# Main.net
KiCad netlist of a schematic drawn in Altium Designer
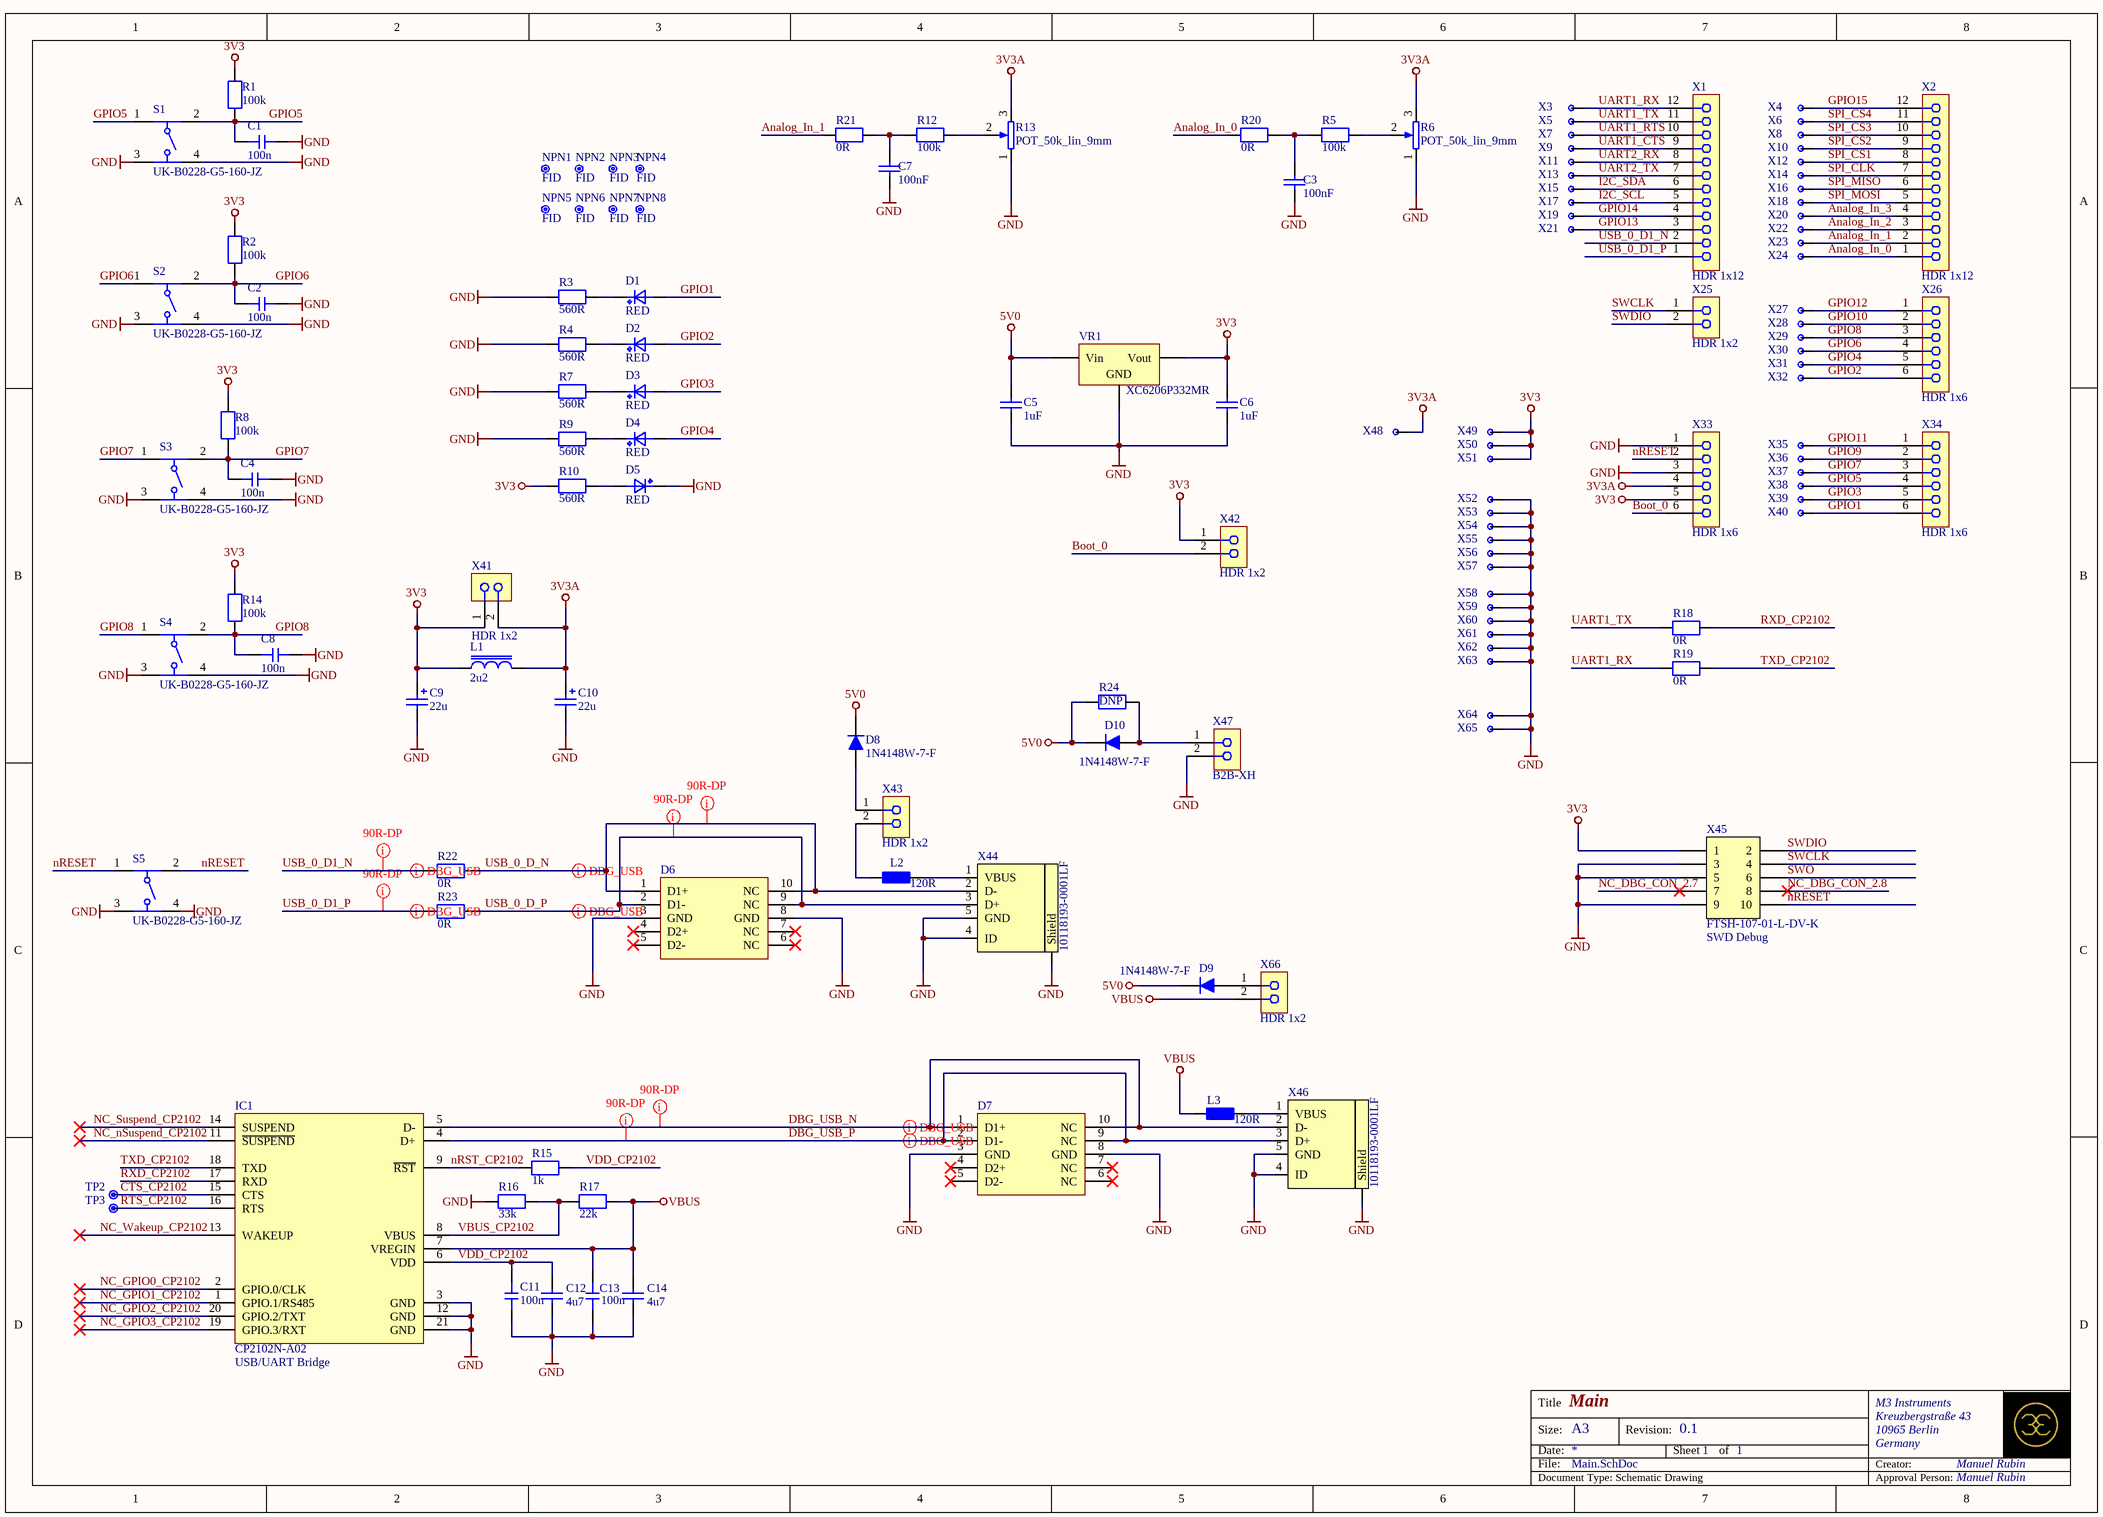
[diagram p0: Main.SchDoc]

(export (version "E")
  (design (tool "Eeschema 10.0.6"))
  (components
    (comp (ref "C1")
      (value "100n")
      (footprint "CAPC1608X95N")
      (description "100n_50V")
      (fields (field (name "MANUFACTURER") "AVX") (field (name "MANUFACTURER PART NUMBER") "06031C104KAT2A"))
      (libsource (lib "Raindancer") (part "C_100n_50V_0603"))
    )
    (comp (ref "C2")
      (value "100n")
      (footprint "CAPC1608X95N")
      (description "100n_50V")
      (fields (field (name "MANUFACTURER") "AVX") (field (name "MANUFACTURER PART NUMBER") "06031C104KAT2A"))
      (libsource (lib "Raindancer") (part "C_100n_50V_0603"))
    )
    (comp (ref "C3")
      (value "100nF")
      (footprint "CAPC1608X95N")
      (description "Multilayer Ceramic Capacitors MLCC - SMD/SMT, 100nF")
      (fields
        (field (name "MANUFACTURER") "YAGEO")
        (field (name "MANUFACTURER PART NUMBER") "CC0603KRX7R9BB104")
      )
      (libsource (lib "Caps") (part "CAP_100nF_0603"))
    )
    (comp (ref "C4")
      (value "100n")
      (footprint "CAPC1608X95N")
      (description "100n_50V")
      (fields (field (name "MANUFACTURER") "AVX") (field (name "MANUFACTURER PART NUMBER") "06031C104KAT2A"))
      (libsource (lib "Raindancer") (part "C_100n_50V_0603"))
    )
    (comp (ref "C5")
      (value "1uF")
      (footprint "CAPC2012X145N")
      (description "Multilayer Ceramic Capacitors MLCC - SMD/SMT, 1uF")
      (fields (field (name "MANUFACTURER") "Samsung Electro-Mechanics") (field (name "TOLERANCE") "10%"))
      (libsource (lib "Caps") (part "CAP_1uF_0805"))
    )
    (comp (ref "C6")
      (value "1uF")
      (footprint "CAPC2012X145N")
      (description "Multilayer Ceramic Capacitors MLCC - SMD/SMT, 1uF")
      (fields (field (name "MANUFACTURER") "Samsung Electro-Mechanics") (field (name "TOLERANCE") "10%"))
      (libsource (lib "Caps") (part "CAP_1uF_0805"))
    )
    (comp (ref "C7")
      (value "100nF")
      (footprint "CAPC1608X95N")
      (description "Multilayer Ceramic Capacitors MLCC - SMD/SMT, 100nF")
      (fields
        (field (name "MANUFACTURER") "YAGEO")
        (field (name "MANUFACTURER PART NUMBER") "CC0603KRX7R9BB104")
      )
      (libsource (lib "Caps") (part "CAP_100nF_0603"))
    )
    (comp (ref "C8")
      (value "100n")
      (footprint "CAPC1608X95N")
      (description "100n_50V")
      (fields (field (name "MANUFACTURER") "AVX") (field (name "MANUFACTURER PART NUMBER") "06031C104KAT2A"))
      (libsource (lib "Raindancer") (part "C_100n_50V_0603"))
    )
    (comp (ref "C9")
      (value "22u")
      (footprint "CAPAE4643X54M")
      (description "Aluminium Electrolytic Capacitors - SMD 22UF 16V HA SMD")
      (fields
        (field (name "MANUFACTURER") "Panasonic")
        (field (name "MANUFACTURER PART NUMBER") "EEE-HAC220WAR")
      )
      (libsource (lib "Caps") (part "CAP_22u"))
    )
    (comp (ref "C10")
      (value "22u")
      (footprint "CAPAE4643X54M")
      (description "Aluminium Electrolytic Capacitors - SMD 22UF 16V HA SMD")
      (fields
        (field (name "MANUFACTURER") "Panasonic")
        (field (name "MANUFACTURER PART NUMBER") "EEE-HAC220WAR")
      )
      (libsource (lib "Caps") (part "CAP_22u"))
    )
    (comp (ref "C11")
      (value "100n")
      (footprint "CAPC1608X95N")
      (description "100n_50V")
      (fields (field (name "MANUFACTURER") "AVX") (field (name "MANUFACTURER PART NUMBER") "06031C104KAT2A"))
      (libsource (lib "Raindancer") (part "C_100n_50V_0603"))
    )
    (comp (ref "C12")
      (value "4u7")
      (footprint "CAPC1608X95N")
      (description "16V 4.7uF X5R ±10% 0603 Multilayer Ceramic Capacitors MLCC - SMD/SMT ROHS")
      (fields
        (field (name "MANUFACTURER") "Murata Electronics")
        (field (name "MANUFACTURER PART NUMBER") "GRM188C81C475KE11D")
      )
      (libsource (lib "Caps") (part "CAP_4u7_0603"))
    )
    (comp (ref "C13")
      (value "100n")
      (footprint "CAPC1608X95N")
      (description "100n_50V")
      (fields (field (name "MANUFACTURER") "AVX") (field (name "MANUFACTURER PART NUMBER") "06031C104KAT2A"))
      (libsource (lib "Raindancer") (part "C_100n_50V_0603"))
    )
    (comp (ref "C14")
      (value "4u7")
      (footprint "CAPC1608X95N")
      (description "16V 4.7uF X5R ±10% 0603 Multilayer Ceramic Capacitors MLCC - SMD/SMT ROHS")
      (fields
        (field (name "MANUFACTURER") "Murata Electronics")
        (field (name "MANUFACTURER PART NUMBER") "GRM188C81C475KE11D")
      )
      (libsource (lib "Caps") (part "CAP_4u7_0603"))
    )
    (comp (ref "D1")
      (value "RED")
      (footprint "WL-SMCW_0805")
      (description "Standard LEDs - SMD WL-SMCW SMDMono TpVw Waterclr 0805 Red")
      (fields
        (field (name "MANUFACTURER") "Wurth Elektronik")
        (field (name "MANUFACTURER PART NUMBER") "150080RS75000")
      )
      (libsource (lib "Diodes") (part "LED_0805_RED_AK"))
    )
    (comp (ref "D2")
      (value "RED")
      (footprint "WL-SMCW_0805")
      (description "Standard LEDs - SMD WL-SMCW SMDMono TpVw Waterclr 0805 Red")
      (fields
        (field (name "MANUFACTURER") "Wurth Elektronik")
        (field (name "MANUFACTURER PART NUMBER") "150080RS75000")
      )
      (libsource (lib "Diodes") (part "LED_0805_RED_AK"))
    )
    (comp (ref "D3")
      (value "RED")
      (footprint "WL-SMCW_0805")
      (description "Standard LEDs - SMD WL-SMCW SMDMono TpVw Waterclr 0805 Red")
      (fields
        (field (name "MANUFACTURER") "Wurth Elektronik")
        (field (name "MANUFACTURER PART NUMBER") "150080RS75000")
      )
      (libsource (lib "Diodes") (part "LED_0805_RED_AK"))
    )
    (comp (ref "D4")
      (value "RED")
      (footprint "WL-SMCW_0805")
      (description "Standard LEDs - SMD WL-SMCW SMDMono TpVw Waterclr 0805 Red")
      (fields
        (field (name "MANUFACTURER") "Wurth Elektronik")
        (field (name "MANUFACTURER PART NUMBER") "150080RS75000")
      )
      (libsource (lib "Diodes") (part "LED_0805_RED_AK"))
    )
    (comp (ref "D5")
      (value "RED")
      (footprint "WL-SMCW_0805")
      (description "Standard LEDs - SMD WL-SMCW SMDMono TpVw Waterclr 0805 Red")
      (fields
        (field (name "MANUFACTURER") "Wurth Elektronik")
        (field (name "MANUFACTURER PART NUMBER") "150080RS75000")
      )
      (libsource (lib "Diodes") (part "LED_0805_RED_AK"))
    )
    (comp (ref "D6")
      (value "~")
      (footprint "DQA R-PUSON-N10")
      (description "2-, 4-Channel ESD Protection for Super-Speed USB 3.0 Interface")
      (fields
        (field (name "MANUFACTURER") "Texas Instruments")
        (field (name "MANUFACTURER PART NUMBER") "TPD4EUSB30DQAR")
      )
      (libsource (lib "Diodes") (part "TPD4EUSB30DQAR"))
    )
    (comp (ref "D7")
      (value "~")
      (footprint "DQA R-PUSON-N10")
      (description "2-, 4-Channel ESD Protection for Super-Speed USB 3.0 Interface")
      (fields
        (field (name "MANUFACTURER") "Texas Instruments")
        (field (name "MANUFACTURER PART NUMBER") "TPD4EUSB30DQAR")
      )
      (libsource (lib "Diodes") (part "TPD4EUSB30DQAR"))
    )
    (comp (ref "D8")
      (value "1N4148W-7-F")
      (footprint "SOD-123")
      (description "Diodes - General Purpose, Power, Switching SURFACE MOUNT FAST SWITCHING DIODE 2A")
      (fields (field (name "MANUFACTURER") "Diodes Incorporated"))
      (libsource (lib "Diodes") (part "1N4148W-7-F"))
    )
    (comp (ref "D9")
      (value "1N4148W-7-F")
      (footprint "SOD-123")
      (description "Diodes - General Purpose, Power, Switching SURFACE MOUNT FAST SWITCHING DIODE 2A")
      (fields (field (name "MANUFACTURER") "Diodes Incorporated"))
      (libsource (lib "Diodes") (part "1N4148W-7-F"))
    )
    (comp (ref "D10")
      (value "1N4148W-7-F")
      (footprint "SOD-123")
      (description "Diodes - General Purpose, Power, Switching SURFACE MOUNT FAST SWITCHING DIODE 2A")
      (fields (field (name "MANUFACTURER") "Diodes Incorporated"))
      (libsource (lib "Diodes") (part "1N4148W-7-F"))
    )
    (comp (ref "IC1")
      (value "CP2102N-A02")
      (footprint "SILABS_CP2102N-A02-GQFN20R")
      (description "USB Interface IC USBXpress - USB to UART Bridge QFN28")
      (fields
        (field (name "MANUFACTURER") "Silicon Labs")
        (field (name "MANUFACTURER PART NUMBER") "CP2102N-A02-GQFN20R")
        (field (name "DEVNOTE") "USB/UART Bridge")
      )
      (libsource (lib "Raindancer") (part "IC_CP2102N-A02-QFN20"))
    )
    (comp (ref "L1")
      (value "2u2")
      (footprint "INDP5050X39N")
      (description "Fixed Inductors 2.2uH 3.8A")
      (fields
        (field (name "MANUFACTURER") "Bourns")
        (field (name "MANUFACTURER PART NUMBER") "SRN5040TA-2R2M")
      )
      (libsource (lib "Inductors") (part "IND_2u2_3.8A"))
    )
    (comp (ref "L2")
      (value "120R")
      (footprint "INDC1608X95AN")
      (description "Chip Bead Inductors for Power Lines")
      (fields
        (field (name "MANUFACTURER") "Taiyo Yuden")
        (field (name "MANUFACTURER PART NUMBER") "FBMH1608HL121-T")
      )
      (libsource (lib "Inductors") (part "FB_600R_0603"))
    )
    (comp (ref "L3")
      (value "120R")
      (footprint "INDC1608X95AN")
      (description "Chip Bead Inductors for Power Lines")
      (fields
        (field (name "MANUFACTURER") "Taiyo Yuden")
        (field (name "MANUFACTURER PART NUMBER") "FBMH1608HL121-T")
      )
      (libsource (lib "Inductors") (part "FB_600R_0603"))
    )
    (comp (ref "NPN1")
      (value "FID")
      (footprint "Fiducial_1mm")
      (libsource (lib "MISC") (part "Fiducial_1mm"))
    )
    (comp (ref "NPN2")
      (value "FID")
      (footprint "Fiducial_1mm")
      (libsource (lib "MISC") (part "Fiducial_1mm"))
    )
    (comp (ref "NPN3")
      (value "FID")
      (footprint "Fiducial_1mm")
      (libsource (lib "MISC") (part "Fiducial_1mm"))
    )
    (comp (ref "NPN4")
      (value "FID")
      (footprint "Fiducial_1mm")
      (libsource (lib "MISC") (part "Fiducial_1mm"))
    )
    (comp (ref "NPN5")
      (value "FID")
      (footprint "Fiducial_1mm")
      (libsource (lib "MISC") (part "Fiducial_1mm"))
    )
    (comp (ref "NPN6")
      (value "FID")
      (footprint "Fiducial_1mm")
      (libsource (lib "MISC") (part "Fiducial_1mm"))
    )
    (comp (ref "NPN7")
      (value "FID")
      (footprint "Fiducial_1mm")
      (libsource (lib "MISC") (part "Fiducial_1mm"))
    )
    (comp (ref "NPN8")
      (value "FID")
      (footprint "Fiducial_1mm")
      (libsource (lib "MISC") (part "Fiducial_1mm"))
    )
    (comp (ref "R1")
      (value "100k")
      (footprint "RESC2012X70N")
      (description "Thick Film Resistors - SMD 1/8watt 100Kohms 1% 100ppm")
      (fields
        (field (name "MANUFACTURER") "Vishay / Dale")
        (field (name "MANUFACTURER PART NUMBER") "CRCW0805100KFKEA")
      )
      (libsource (lib "Resistors") (part "RES_100k_0805"))
    )
    (comp (ref "R2")
      (value "100k")
      (footprint "RESC2012X70N")
      (description "Thick Film Resistors - SMD 1/8watt 100Kohms 1% 100ppm")
      (fields
        (field (name "MANUFACTURER") "Vishay / Dale")
        (field (name "MANUFACTURER PART NUMBER") "CRCW0805100KFKEA")
      )
      (libsource (lib "Resistors") (part "RES_100k_0805"))
    )
    (comp (ref "R3")
      (value "560R")
      (footprint "RESC1608X55N")
      (description "Thick Film Resistors - SMD 560 Ohms 125 mW 0603")
      (fields
        (field (name "MANUFACTURER") "ROHM Semicon")
        (field (name "MANUFACTURER PART NUMBER") "MCR03ERTF5600")
      )
      (libsource (lib "Resistors") (part "RES_560R_0603"))
    )
    (comp (ref "R4")
      (value "560R")
      (footprint "RESC1608X55N")
      (description "Thick Film Resistors - SMD 560 Ohms 125 mW 0603")
      (fields
        (field (name "MANUFACTURER") "ROHM Semicon")
        (field (name "MANUFACTURER PART NUMBER") "MCR03ERTF5600")
      )
      (libsource (lib "Resistors") (part "RES_560R_0603"))
    )
    (comp (ref "R5")
      (value "100k")
      (footprint "RESC2012X70N")
      (description "Thick Film Resistors - SMD 1/8watt 100Kohms 1% 100ppm")
      (fields
        (field (name "MANUFACTURER") "Vishay / Dale")
        (field (name "MANUFACTURER PART NUMBER") "CRCW0805100KFKEA")
      )
      (libsource (lib "") (part "RES_100k_0805_1"))
    )
    (comp (ref "R6")
      (value "POT_50k_lin_9mm")
      (footprint "PTV09")
      (description "PTV09A-4020F-A203 50k, 20mm")
      (fields
        (field (name "MANUFACTURER") "Bourns")
        (field (name "MANUFACTURER PART NUMBER") "PTV09A-5020F-A503")
      )
      (libsource (lib "Resistors") (part "POT_50k_lin_9mm"))
    )
    (comp (ref "R7")
      (value "560R")
      (footprint "RESC1608X55N")
      (description "Thick Film Resistors - SMD 560 Ohms 125 mW 0603")
      (fields
        (field (name "MANUFACTURER") "ROHM Semicon")
        (field (name "MANUFACTURER PART NUMBER") "MCR03ERTF5600")
      )
      (libsource (lib "Resistors") (part "RES_560R_0603"))
    )
    (comp (ref "R8")
      (value "100k")
      (footprint "RESC2012X70N")
      (description "Thick Film Resistors - SMD 1/8watt 100Kohms 1% 100ppm")
      (fields
        (field (name "MANUFACTURER") "Vishay / Dale")
        (field (name "MANUFACTURER PART NUMBER") "CRCW0805100KFKEA")
      )
      (libsource (lib "Resistors") (part "RES_100k_0805"))
    )
    (comp (ref "R9")
      (value "560R")
      (footprint "RESC1608X55N")
      (description "Thick Film Resistors - SMD 560 Ohms 125 mW 0603")
      (fields
        (field (name "MANUFACTURER") "ROHM Semicon")
        (field (name "MANUFACTURER PART NUMBER") "MCR03ERTF5600")
      )
      (libsource (lib "Resistors") (part "RES_560R_0603"))
    )
    (comp (ref "R10")
      (value "560R")
      (footprint "RESC1608X55N")
      (description "Thick Film Resistors - SMD 560 Ohms 125 mW 0603")
      (fields
        (field (name "MANUFACTURER") "ROHM Semicon")
        (field (name "MANUFACTURER PART NUMBER") "MCR03ERTF5600")
      )
      (libsource (lib "Resistors") (part "RES_560R_0603"))
    )
    (comp (ref "R12")
      (value "100k")
      (footprint "RESC2012X70N")
      (description "Thick Film Resistors - SMD 1/8watt 100Kohms 1% 100ppm")
      (fields
        (field (name "MANUFACTURER") "Vishay / Dale")
        (field (name "MANUFACTURER PART NUMBER") "CRCW0805100KFKEA")
      )
      (libsource (lib "") (part "RES_100k_0805_1"))
    )
    (comp (ref "R13")
      (value "POT_50k_lin_9mm")
      (footprint "PTV09")
      (description "PTV09A-4020F-A203 50k, 20mm")
      (fields
        (field (name "MANUFACTURER") "Bourns")
        (field (name "MANUFACTURER PART NUMBER") "PTV09A-5020F-A503")
      )
      (libsource (lib "Resistors") (part "POT_50k_lin_9mm"))
    )
    (comp (ref "R14")
      (value "100k")
      (footprint "RESC2012X70N")
      (description "Thick Film Resistors - SMD 1/8watt 100Kohms 1% 100ppm")
      (fields
        (field (name "MANUFACTURER") "Vishay / Dale")
        (field (name "MANUFACTURER PART NUMBER") "CRCW0805100KFKEA")
      )
      (libsource (lib "Resistors") (part "RES_100k_0805"))
    )
    (comp (ref "R15")
      (value "1k")
      (footprint "RESC1608X55AN")
      (description "Thick Film Resistors - SMD 1 kOhms 100mW 0603 1%")
      (fields
        (field (name "MANUFACTURER") "Yageo")
        (field (name "MANUFACTURER PART NUMBER") "RC0603FR-071KL")
      )
      (libsource (lib "Raindancer") (part "RES_1k_0603"))
    )
    (comp (ref "R16")
      (value "33k")
      (footprint "RESC1608X55AN")
      (description "Thick Film Resistors - SMD 33 kOhms 100 mW 0603 5%")
      (fields
        (field (name "MANUFACTURER") "YAGEO")
        (field (name "MANUFACTURER PART NUMBER") "RC0603JR-0733KL")
      )
      (libsource (lib "Raindancer") (part "RES_33k_0603"))
    )
    (comp (ref "R17")
      (value "22k")
      (footprint "RESC1608X55AN")
      (description "Thick Film Resistors - SMD 22kOhms 1/10W 0603 1%")
      (fields
        (field (name "MANUFACTURER") "YAGEO")
        (field (name "MANUFACTURER PART NUMBER") "RC0603FR-7W22KL")
      )
      (libsource (lib "Raindancer") (part "RES_22k_0603"))
    )
    (comp (ref "R18")
      (value "0R")
      (footprint "RESC1608X55N")
      (description "Thick Film Resistors - SMD 1/10watt ZEROohm Jumper")
      (fields
        (field (name "MANUFACTURER") "Vishay")
        (field (name "MANUFACTURER PART NUMBER") "CRCW06030000Z0EA")
      )
      (libsource (lib "Resistors") (part "RES_0R_0603"))
    )
    (comp (ref "R19")
      (value "0R")
      (footprint "RESC1608X55N")
      (description "Thick Film Resistors - SMD 1/10watt ZEROohm Jumper")
      (fields
        (field (name "MANUFACTURER") "Vishay")
        (field (name "MANUFACTURER PART NUMBER") "CRCW06030000Z0EA")
      )
      (libsource (lib "Resistors") (part "RES_0R_0603"))
    )
    (comp (ref "R20")
      (value "0R")
      (footprint "RESC1608X55N")
      (description "Thick Film Resistors - SMD 1/10watt ZEROohm Jumper")
      (fields
        (field (name "MANUFACTURER") "Vishay")
        (field (name "MANUFACTURER PART NUMBER") "CRCW06030000Z0EA")
      )
      (libsource (lib "Resistors") (part "RES_0R_0603"))
    )
    (comp (ref "R21")
      (value "0R")
      (footprint "RESC1608X55N")
      (description "Thick Film Resistors - SMD 1/10watt ZEROohm Jumper")
      (fields
        (field (name "MANUFACTURER") "Vishay")
        (field (name "MANUFACTURER PART NUMBER") "CRCW06030000Z0EA")
      )
      (libsource (lib "Resistors") (part "RES_0R_0603"))
    )
    (comp (ref "R22")
      (value "0R")
      (footprint "RESC1608X55N")
      (description "Thick Film Resistors - SMD 1/10watt ZEROohm Jumper")
      (fields
        (field (name "MANUFACTURER") "Vishay")
        (field (name "MANUFACTURER PART NUMBER") "CRCW06030000Z0EA")
      )
      (libsource (lib "Resistors") (part "RES_0R_0603"))
    )
    (comp (ref "R23")
      (value "0R")
      (footprint "RESC1608X55N")
      (description "Thick Film Resistors - SMD 1/10watt ZEROohm Jumper")
      (fields
        (field (name "MANUFACTURER") "Vishay")
        (field (name "MANUFACTURER PART NUMBER") "CRCW06030000Z0EA")
      )
      (libsource (lib "Resistors") (part "RES_0R_0603"))
    )
    (comp (ref "R24")
      (value "DNP")
      (footprint "RESC2012X70N")
      (description "Resistor SMD 0805 - not populated")
      (libsource (lib "Resistors") (part "RES_DNF_0805"))
    )
    (comp (ref "S1")
      (value "UK-B0228-G5-160-JZ")
      (footprint "UK-B0228-G5-160-JZ")
      (fields (field (name "MANUFACTURER") "USAKRO"))
      (libsource (lib "Switches") (part "SW_UK-B0228-G5-160-JZ"))
    )
    (comp (ref "S2")
      (value "UK-B0228-G5-160-JZ")
      (footprint "UK-B0228-G5-160-JZ")
      (fields (field (name "MANUFACTURER") "USAKRO"))
      (libsource (lib "Switches") (part "SW_UK-B0228-G5-160-JZ"))
    )
    (comp (ref "S3")
      (value "UK-B0228-G5-160-JZ")
      (footprint "UK-B0228-G5-160-JZ")
      (fields (field (name "MANUFACTURER") "USAKRO"))
      (libsource (lib "Switches") (part "SW_UK-B0228-G5-160-JZ"))
    )
    (comp (ref "S4")
      (value "UK-B0228-G5-160-JZ")
      (footprint "UK-B0228-G5-160-JZ")
      (fields (field (name "MANUFACTURER") "USAKRO"))
      (libsource (lib "Switches") (part "SW_UK-B0228-G5-160-JZ"))
    )
    (comp (ref "S5")
      (value "UK-B0228-G5-160-JZ")
      (footprint "UK-B0228-G5-160-JZ")
      (fields (field (name "MANUFACTURER") "USAKRO"))
      (libsource (lib "Switches") (part "SW_UK-B0228-G5-160-JZ"))
    )
    (comp (ref "TP2")
      (value "TP 0.7mm")
      (footprint "TP_0.7mm")
      (description "Test Pad surface mount")
      (libsource (lib "Raindancer") (part "MISC_Test Pad 0.7mm"))
    )
    (comp (ref "TP3")
      (value "TP 0.7mm")
      (footprint "TP_0.7mm")
      (description "Test Pad surface mount")
      (libsource (lib "Raindancer") (part "MISC_Test Pad 0.7mm"))
    )
    (comp (ref "VR1")
      (value "XC6206P332MR")
      (footprint "SOT95P280X135-3N_123")
      (description "LOW DROPOUT REGULATORS(LDO) POSITIVE FIXED 680MV @ 100MA 6V 3.3V 200MA SOT-23-3L ROHS")
      (fields (field (name "MANUFACTURER") "Torex Semicon"))
      (libsource (lib "ICs") (part "IC_XC6206P332MR"))
    )
    (comp (ref "X1")
      (value "HDR 1x12")
      (footprint "61301211821_NO")
      (description "Board-to-Board-Steckverbinder, 2.54 mm, 12 Kontakt(e), Stiftleiste 1-Reihig")
      (fields (field (name "MANUFACTURER") "WE") (field (name "MANUFACTURER PART NUMBER") "61301211821"))
      (libsource (lib "Connectors") (part "CON_HEADER_1X12_FEMALE_NO"))
    )
    (comp (ref "X2")
      (value "HDR 1x12")
      (footprint "61301211821_NO")
      (description "Board-to-Board-Steckverbinder, 2.54 mm, 12 Kontakt(e), Stiftleiste 1-Reihig")
      (fields (field (name "MANUFACTURER") "WE") (field (name "MANUFACTURER PART NUMBER") "61301211821"))
      (libsource (lib "Connectors") (part "CON_HEADER_1X12_FEMALE_NO"))
    )
    (comp (ref "X3") (value "PAD") (footprint "PAD_1.1_1.6") (libsource (lib "MISC") (part "PAD_2.54")))
    (comp (ref "X4") (value "PAD") (footprint "PAD_1.1_1.6") (libsource (lib "MISC") (part "PAD_2.54")))
    (comp (ref "X5") (value "PAD") (footprint "PAD_1.1_1.6") (libsource (lib "MISC") (part "PAD_2.54")))
    (comp (ref "X6") (value "PAD") (footprint "PAD_1.1_1.6") (libsource (lib "MISC") (part "PAD_2.54")))
    (comp (ref "X7") (value "PAD") (footprint "PAD_1.1_1.6") (libsource (lib "MISC") (part "PAD_2.54")))
    (comp (ref "X8") (value "PAD") (footprint "PAD_1.1_1.6") (libsource (lib "MISC") (part "PAD_2.54")))
    (comp (ref "X9") (value "PAD") (footprint "PAD_1.1_1.6") (libsource (lib "MISC") (part "PAD_2.54")))
    (comp (ref "X10") (value "PAD") (footprint "PAD_1.1_1.6") (libsource (lib "MISC") (part "PAD_2.54")))
    (comp (ref "X11") (value "PAD") (footprint "PAD_1.1_1.6") (libsource (lib "MISC") (part "PAD_2.54")))
    (comp (ref "X12") (value "PAD") (footprint "PAD_1.1_1.6") (libsource (lib "MISC") (part "PAD_2.54")))
    (comp (ref "X13") (value "PAD") (footprint "PAD_1.1_1.6") (libsource (lib "MISC") (part "PAD_2.54")))
    (comp (ref "X14") (value "PAD") (footprint "PAD_1.1_1.6") (libsource (lib "MISC") (part "PAD_2.54")))
    (comp (ref "X15") (value "PAD") (footprint "PAD_1.1_1.6") (libsource (lib "MISC") (part "PAD_2.54")))
    (comp (ref "X16") (value "PAD") (footprint "PAD_1.1_1.6") (libsource (lib "MISC") (part "PAD_2.54")))
    (comp (ref "X17") (value "PAD") (footprint "PAD_1.1_1.6") (libsource (lib "MISC") (part "PAD_2.54")))
    (comp (ref "X18") (value "PAD") (footprint "PAD_1.1_1.6") (libsource (lib "MISC") (part "PAD_2.54")))
    (comp (ref "X19") (value "PAD") (footprint "PAD_1.1_1.6") (libsource (lib "MISC") (part "PAD_2.54")))
    (comp (ref "X20") (value "PAD") (footprint "PAD_1.1_1.6") (libsource (lib "MISC") (part "PAD_2.54")))
    (comp (ref "X21") (value "PAD") (footprint "PAD_1.1_1.6") (libsource (lib "MISC") (part "PAD_2.54")))
    (comp (ref "X22") (value "PAD") (footprint "PAD_1.1_1.6") (libsource (lib "MISC") (part "PAD_2.54")))
    (comp (ref "X23") (value "PAD") (footprint "PAD_1.1_1.6") (libsource (lib "MISC") (part "PAD_2.54")))
    (comp (ref "X24") (value "PAD") (footprint "PAD_1.1_1.6") (libsource (lib "MISC") (part "PAD_2.54")))
    (comp (ref "X25")
      (value "HDR 1x2")
      (footprint "61300211821_NO")
      (description "Board-to-Board-Steckverbinder, 2.54 mm, 2 Kontakt(e), Stiftleiste 1-Reihig")
      (fields (field (name "MANUFACTURER") "WE") (field (name "MANUFACTURER PART NUMBER") "61300211821"))
      (libsource (lib "Connectors") (part "CON_HEADER_1X2_FEMALE_NO"))
    )
    (comp (ref "X26")
      (value "HDR 1x6")
      (footprint "61300611821_NO")
      (description "Board-to-Board-Steckverbinder, 2.54 mm, 6 Kontakt(e), Stiftleiste 1-Reihig")
      (fields (field (name "MANUFACTURER") "WE") (field (name "MANUFACTURER PART NUMBER") "61300611821"))
      (libsource (lib "Connectors") (part "CON_HEADER_1X6_FEMALE_NO"))
    )
    (comp (ref "X27") (value "PAD") (footprint "PAD_1.1_1.6") (libsource (lib "MISC") (part "PAD_2.54")))
    (comp (ref "X28") (value "PAD") (footprint "PAD_1.1_1.6") (libsource (lib "MISC") (part "PAD_2.54")))
    (comp (ref "X29") (value "PAD") (footprint "PAD_1.1_1.6") (libsource (lib "MISC") (part "PAD_2.54")))
    (comp (ref "X30") (value "PAD") (footprint "PAD_1.1_1.6") (libsource (lib "MISC") (part "PAD_2.54")))
    (comp (ref "X31") (value "PAD") (footprint "PAD_1.1_1.6") (libsource (lib "MISC") (part "PAD_2.54")))
    (comp (ref "X32") (value "PAD") (footprint "PAD_1.1_1.6") (libsource (lib "MISC") (part "PAD_2.54")))
    (comp (ref "X33")
      (value "HDR 1x6")
      (footprint "61300611821_NO")
      (description "Board-to-Board-Steckverbinder, 2.54 mm, 6 Kontakt(e), Stiftleiste 1-Reihig")
      (fields (field (name "MANUFACTURER") "WE") (field (name "MANUFACTURER PART NUMBER") "61300611821"))
      (libsource (lib "Connectors") (part "CON_HEADER_1X6_FEMALE_NO"))
    )
    (comp (ref "X34")
      (value "HDR 1x6")
      (footprint "61300611821_NO")
      (description "Board-to-Board-Steckverbinder, 2.54 mm, 6 Kontakt(e), Stiftleiste 1-Reihig")
      (fields (field (name "MANUFACTURER") "WE") (field (name "MANUFACTURER PART NUMBER") "61300611821"))
      (libsource (lib "Connectors") (part "CON_HEADER_1X6_FEMALE_NO"))
    )
    (comp (ref "X35") (value "PAD") (footprint "PAD_1.1_1.6") (libsource (lib "MISC") (part "PAD_2.54")))
    (comp (ref "X36") (value "PAD") (footprint "PAD_1.1_1.6") (libsource (lib "MISC") (part "PAD_2.54")))
    (comp (ref "X37") (value "PAD") (footprint "PAD_1.1_1.6") (libsource (lib "MISC") (part "PAD_2.54")))
    (comp (ref "X38") (value "PAD") (footprint "PAD_1.1_1.6") (libsource (lib "MISC") (part "PAD_2.54")))
    (comp (ref "X39") (value "PAD") (footprint "PAD_1.1_1.6") (libsource (lib "MISC") (part "PAD_2.54")))
    (comp (ref "X40") (value "PAD") (footprint "PAD_1.1_1.6") (libsource (lib "MISC") (part "PAD_2.54")))
    (comp (ref "X41")
      (value "HDR 1x2")
      (footprint "CON_HEADER2.54_1x2W")
      (description "Board-to-Board-Steckverbinder, 2.54 mm, 2 Kontakt(e), Stiftleiste 1-Reihig")
      (fields
        (field (name "MANUFACTURER") "Samtec")
        (field (name "MANUFACTURER PART NUMBER") "TSW-102-07-T-S")
      )
      (libsource (lib "Connectors") (part "CON_HEADER_1X2"))
    )
    (comp (ref "X42")
      (value "HDR 1x2")
      (footprint "CON_HEADER2.54_1x2W")
      (description "Board-to-Board-Steckverbinder, 2.54 mm, 2 Kontakt(e), Stiftleiste 1-Reihig")
      (fields
        (field (name "MANUFACTURER") "Samtec")
        (field (name "MANUFACTURER PART NUMBER") "TSW-102-07-T-S")
      )
      (libsource (lib "") (part "CON_HEADER_1X2_1"))
    )
    (comp (ref "X43")
      (value "HDR 1x2")
      (footprint "CON_HEADER2.54_1x2W")
      (description "Board-to-Board-Steckverbinder, 2.54 mm, 2 Kontakt(e), Stiftleiste 1-Reihig")
      (fields
        (field (name "MANUFACTURER") "Samtec")
        (field (name "MANUFACTURER PART NUMBER") "TSW-102-07-T-S")
      )
      (libsource (lib "") (part "CON_HEADER_1X2_1"))
    )
    (comp (ref "X44")
      (value "10118193-0001LF")
      (footprint "USB-Micro-B-RA-SMD-PiP")
      (description "MicroUSB-B-SMT")
      (fields (field (name "MANUFACTURER") "Amphenol ICC (FCI)"))
      (libsource (lib "Connectors") (part "CON_MiniUSB-AB-SMT"))
    )
    (comp (ref "X45")
      (value "FTSH-107-01-L-DV-K")
      (footprint "HDR_2x5-SMD-1.27mm-K")
      (description "Pin Header 2x5, 1.27mm (50mil), SMD, Keying Shroud")
      (fields
        (field (name "MANUFACTURER") "Samtec")
        (field (name "MANUFACTURER PART NUMBER") "FTSH-105-01-L-DV-K")
        (field (name "DEVNOTE") "SWD Debug")
      )
      (libsource (lib "Raindancer") (part "CON_2x5_SMD_1.27mm"))
    )
    (comp (ref "X46")
      (value "10118193-0001LF")
      (footprint "USB-Micro-B-RA-SMD-PiP")
      (description "MicroUSB-B-SMT")
      (fields (field (name "MANUFACTURER") "Amphenol ICC (FCI)"))
      (libsource (lib "Connectors") (part "CON_MiniUSB-AB-SMT"))
    )
    (comp (ref "X47")
      (value "B2B-XH")
      (footprint "JST_B2B-XH-A_(LF)(SN)")
      (description "Connector Header Through Hole 2 position 0.098\" (2.50mm)")
      (fields
        (field (name "MANUFACTURER") "JST")
        (field (name "MANUFACTURER PART NUMBER") "B2B-XH-A (LF)(SN)")
      )
      (libsource (lib "Connectors") (part "CON_JST_B2B-XH"))
    )
    (comp (ref "X48") (value "PAD") (footprint "PAD_1.1_1.6") (libsource (lib "MISC") (part "PAD_2.54")))
    (comp (ref "X49") (value "PAD") (footprint "PAD_1.1_1.6") (libsource (lib "MISC") (part "PAD_2.54")))
    (comp (ref "X50") (value "PAD") (footprint "PAD_1.1_1.6") (libsource (lib "MISC") (part "PAD_2.54")))
    (comp (ref "X51") (value "PAD") (footprint "PAD_1.1_1.6") (libsource (lib "MISC") (part "PAD_2.54")))
    (comp (ref "X52") (value "PAD") (footprint "PAD_1.1_1.6") (libsource (lib "MISC") (part "PAD_2.54")))
    (comp (ref "X53") (value "PAD") (footprint "PAD_1.1_1.6") (libsource (lib "MISC") (part "PAD_2.54")))
    (comp (ref "X54") (value "PAD") (footprint "PAD_1.1_1.6") (libsource (lib "MISC") (part "PAD_2.54")))
    (comp (ref "X55") (value "PAD") (footprint "PAD_1.1_1.6") (libsource (lib "MISC") (part "PAD_2.54")))
    (comp (ref "X56") (value "PAD") (footprint "PAD_1.1_1.6") (libsource (lib "MISC") (part "PAD_2.54")))
    (comp (ref "X57") (value "PAD") (footprint "PAD_1.1_1.6") (libsource (lib "MISC") (part "PAD_2.54")))
    (comp (ref "X58") (value "PAD") (footprint "PAD_1.1_1.6") (libsource (lib "MISC") (part "PAD_2.54")))
    (comp (ref "X59") (value "PAD") (footprint "PAD_1.1_1.6") (libsource (lib "MISC") (part "PAD_2.54")))
    (comp (ref "X60") (value "PAD") (footprint "PAD_1.1_1.6") (libsource (lib "MISC") (part "PAD_2.54")))
    (comp (ref "X61") (value "PAD") (footprint "PAD_1.1_1.6") (libsource (lib "MISC") (part "PAD_2.54")))
    (comp (ref "X62") (value "PAD") (footprint "PAD_1.1_1.6") (libsource (lib "MISC") (part "PAD_2.54")))
    (comp (ref "X63") (value "PAD") (footprint "PAD_1.1_1.6") (libsource (lib "MISC") (part "PAD_2.54")))
    (comp (ref "X64") (value "PAD") (footprint "PAD_1.1_1.6") (libsource (lib "MISC") (part "PAD_2.54")))
    (comp (ref "X65") (value "PAD") (footprint "PAD_1.1_1.6") (libsource (lib "MISC") (part "PAD_2.54")))
    (comp (ref "X66")
      (value "HDR 1x2")
      (footprint "CON_HEADER2.54_1x2W")
      (description "Board-to-Board-Steckverbinder, 2.54 mm, 2 Kontakt(e), Stiftleiste 1-Reihig")
      (fields
        (field (name "MANUFACTURER") "Samtec")
        (field (name "MANUFACTURER PART NUMBER") "TSW-102-07-T-S")
      )
      (libsource (lib "") (part "CON_HEADER_1X2_1"))
    )
  )
  (nets
    (net (code "1") (name "/Analog_In_0") (class "Default")
      (node (ref "R20") (pin "2") (pinfunction "2_2") (pintype "passive"))
      (node (ref "X2") (pin "1") (pinfunction "1_1") (pintype "passive"))
      (node (ref "X24") (pin "1") (pinfunction "1_1") (pintype "passive"))
    )
    (net (code "2") (name "/Analog_In_1") (class "Default")
      (node (ref "R21") (pin "2") (pinfunction "2_2") (pintype "passive"))
      (node (ref "X2") (pin "2") (pinfunction "2_2") (pintype "passive"))
      (node (ref "X23") (pin "1") (pinfunction "1_1") (pintype "passive"))
    )
    (net (code "3") (name "/Analog_In_2") (class "Default")
      (node (ref "X2") (pin "3") (pinfunction "3_3") (pintype "passive"))
      (node (ref "X22") (pin "1") (pinfunction "1_1") (pintype "passive"))
    )
    (net (code "4") (name "/Analog_In_3") (class "Default")
      (node (ref "X2") (pin "4") (pinfunction "4_4") (pintype "passive"))
      (node (ref "X20") (pin "1") (pinfunction "1_1") (pintype "passive"))
    )
    (net (code "5") (name "/Boot_0") (class "Default")
      (node (ref "X33") (pin "6") (pinfunction "6_6") (pintype "passive"))
      (node (ref "X42") (pin "2") (pinfunction "2_2") (pintype "passive"))
    )
    (net (code "6") (name "/CTS_CP2102") (class "Default")
      (node (ref "IC1") (pin "15") (pinfunction "CTS_15") (pintype "passive"))
      (node (ref "TP2") (pin "1") (pinfunction "1_1") (pintype "passive"))
    )
    (net (code "7") (name "/DBG_USB_N") (class "Default")
      (node (ref "D7") (pin "1") (pinfunction "D1+_1") (pintype "passive"))
      (node (ref "D7") (pin "10") (pinfunction "NC_10") (pintype "passive"))
      (node (ref "IC1") (pin "5") (pinfunction "D-_5") (pintype "passive"))
      (node (ref "X46") (pin "2") (pinfunction "D-_2") (pintype "passive"))
    )
    (net (code "8") (name "/DBG_USB_P") (class "Default")
      (node (ref "D7") (pin "2") (pinfunction "D1-_2") (pintype "passive"))
      (node (ref "D7") (pin "9") (pinfunction "NC_9") (pintype "passive"))
      (node (ref "IC1") (pin "4") (pinfunction "D+_4") (pintype "passive"))
      (node (ref "X46") (pin "3") (pinfunction "D+_3") (pintype "passive"))
    )
    (net (code "9") (name "/GPIO1") (class "Default")
      (node (ref "D1") (pin "A") (pinfunction "A_A") (pintype "passive"))
      (node (ref "X34") (pin "6") (pinfunction "6_6") (pintype "passive"))
      (node (ref "X40") (pin "1") (pinfunction "1_1") (pintype "passive"))
    )
    (net (code "10") (name "/GPIO2") (class "Default")
      (node (ref "D2") (pin "A") (pinfunction "A_A") (pintype "passive"))
      (node (ref "X26") (pin "6") (pinfunction "6_6") (pintype "passive"))
      (node (ref "X32") (pin "1") (pinfunction "1_1") (pintype "passive"))
    )
    (net (code "11") (name "/GPIO3") (class "Default")
      (node (ref "D3") (pin "A") (pinfunction "A_A") (pintype "passive"))
      (node (ref "X34") (pin "5") (pinfunction "5_5") (pintype "passive"))
      (node (ref "X39") (pin "1") (pinfunction "1_1") (pintype "passive"))
    )
    (net (code "12") (name "/GPIO4") (class "Default")
      (node (ref "D4") (pin "A") (pinfunction "A_A") (pintype "passive"))
      (node (ref "X26") (pin "5") (pinfunction "5_5") (pintype "passive"))
      (node (ref "X31") (pin "1") (pinfunction "1_1") (pintype "passive"))
    )
    (net (code "13") (name "/GPIO5") (class "Default")
      (node (ref "C1") (pin "1") (pinfunction "1_1") (pintype "passive"))
      (node (ref "R1") (pin "1") (pinfunction "1_1") (pintype "passive"))
      (node (ref "S1") (pin "1") (pinfunction "1_1") (pintype "passive"))
      (node (ref "S1") (pin "2") (pinfunction "2_2") (pintype "passive"))
      (node (ref "X34") (pin "4") (pinfunction "4_4") (pintype "passive"))
      (node (ref "X38") (pin "1") (pinfunction "1_1") (pintype "passive"))
    )
    (net (code "14") (name "/GPIO6") (class "Default")
      (node (ref "C2") (pin "1") (pinfunction "1_1") (pintype "passive"))
      (node (ref "R2") (pin "1") (pinfunction "1_1") (pintype "passive"))
      (node (ref "S2") (pin "1") (pinfunction "1_1") (pintype "passive"))
      (node (ref "S2") (pin "2") (pinfunction "2_2") (pintype "passive"))
      (node (ref "X26") (pin "4") (pinfunction "4_4") (pintype "passive"))
      (node (ref "X30") (pin "1") (pinfunction "1_1") (pintype "passive"))
    )
    (net (code "15") (name "/GPIO7") (class "Default")
      (node (ref "C4") (pin "1") (pinfunction "1_1") (pintype "passive"))
      (node (ref "R8") (pin "1") (pinfunction "1_1") (pintype "passive"))
      (node (ref "S3") (pin "1") (pinfunction "1_1") (pintype "passive"))
      (node (ref "S3") (pin "2") (pinfunction "2_2") (pintype "passive"))
      (node (ref "X34") (pin "3") (pinfunction "3_3") (pintype "passive"))
      (node (ref "X37") (pin "1") (pinfunction "1_1") (pintype "passive"))
    )
    (net (code "16") (name "/GPIO8") (class "Default")
      (node (ref "C8") (pin "1") (pinfunction "1_1") (pintype "passive"))
      (node (ref "R14") (pin "1") (pinfunction "1_1") (pintype "passive"))
      (node (ref "S4") (pin "1") (pinfunction "1_1") (pintype "passive"))
      (node (ref "S4") (pin "2") (pinfunction "2_2") (pintype "passive"))
      (node (ref "X26") (pin "3") (pinfunction "3_3") (pintype "passive"))
      (node (ref "X29") (pin "1") (pinfunction "1_1") (pintype "passive"))
    )
    (net (code "17") (name "/GPIO9") (class "Default")
      (node (ref "X34") (pin "2") (pinfunction "2_2") (pintype "passive"))
      (node (ref "X36") (pin "1") (pinfunction "1_1") (pintype "passive"))
    )
    (net (code "18") (name "/GPIO10") (class "Default")
      (node (ref "X26") (pin "2") (pinfunction "2_2") (pintype "passive"))
      (node (ref "X28") (pin "1") (pinfunction "1_1") (pintype "passive"))
    )
    (net (code "19") (name "/GPIO11") (class "Default")
      (node (ref "X34") (pin "1") (pinfunction "1_1") (pintype "passive"))
      (node (ref "X35") (pin "1") (pinfunction "1_1") (pintype "passive"))
    )
    (net (code "20") (name "/GPIO12") (class "Default")
      (node (ref "X26") (pin "1") (pinfunction "1_1") (pintype "passive"))
      (node (ref "X27") (pin "1") (pinfunction "1_1") (pintype "passive"))
    )
    (net (code "21") (name "/GPIO13") (class "Default")
      (node (ref "X1") (pin "3") (pinfunction "3_3") (pintype "passive"))
      (node (ref "X21") (pin "1") (pinfunction "1_1") (pintype "passive"))
    )
    (net (code "22") (name "/GPIO14") (class "Default")
      (node (ref "X1") (pin "4") (pinfunction "4_4") (pintype "passive"))
      (node (ref "X19") (pin "1") (pinfunction "1_1") (pintype "passive"))
    )
    (net (code "23") (name "/GPIO15") (class "Default")
      (node (ref "X2") (pin "12") (pinfunction "12_12") (pintype "passive"))
      (node (ref "X4") (pin "1") (pinfunction "1_1") (pintype "passive"))
    )
    (net (code "24") (name "/I2C_SCL") (class "Default")
      (node (ref "X1") (pin "5") (pinfunction "5_5") (pintype "passive"))
      (node (ref "X17") (pin "1") (pinfunction "1_1") (pintype "passive"))
    )
    (net (code "25") (name "/I2C_SDA") (class "Default")
      (node (ref "X1") (pin "6") (pinfunction "6_6") (pintype "passive"))
      (node (ref "X15") (pin "1") (pinfunction "1_1") (pintype "passive"))
    )
    (net (code "26") (name "/NC_DBG_CON_2.7") (class "Default")
      (node (ref "X45") (pin "7") (pinfunction "7_7") (pintype "passive+no_connect"))
    )
    (net (code "27") (name "/NC_DBG_CON_2.8") (class "Default")
      (node (ref "X45") (pin "8") (pinfunction "8_8") (pintype "passive+no_connect"))
    )
    (net (code "28") (name "/NC_GPIO0_CP2102") (class "Default")
      (node (ref "IC1") (pin "2") (pinfunction "GPIO.0/CLK_2") (pintype "passive+no_connect"))
    )
    (net (code "29") (name "/NC_GPIO1_CP2102") (class "Default")
      (node (ref "IC1") (pin "1") (pinfunction "GPIO.1/RS485_1") (pintype "passive+no_connect"))
    )
    (net (code "30") (name "/NC_GPIO2_CP2102") (class "Default")
      (node (ref "IC1") (pin "20") (pinfunction "GPIO.2/TXT_20") (pintype "passive+no_connect"))
    )
    (net (code "31") (name "/NC_GPIO3_CP2102") (class "Default")
      (node (ref "IC1") (pin "19") (pinfunction "GPIO.3/RXT_19") (pintype "passive+no_connect"))
    )
    (net (code "32") (name "/NC_Suspend_CP2102") (class "Default")
      (node (ref "IC1") (pin "14") (pinfunction "SUSPEND_14") (pintype "passive+no_connect"))
    )
    (net (code "33") (name "/NC_Wakeup_CP2102") (class "Default")
      (node (ref "IC1") (pin "13") (pinfunction "WAKEUP_13") (pintype "passive+no_connect"))
    )
    (net (code "34") (name "/NC_nSuspend_CP2102") (class "Default")
      (node (ref "IC1") (pin "11") (pinfunction "~{SUSPEND}_11") (pintype "passive+no_connect"))
    )
    (net (code "35") (name "/RTS_CP2102") (class "Default")
      (node (ref "IC1") (pin "16") (pinfunction "RTS_16") (pintype "passive"))
      (node (ref "TP3") (pin "1") (pinfunction "1_1") (pintype "passive"))
    )
    (net (code "36") (name "/RXD_CP2102") (class "Default")
      (node (ref "IC1") (pin "17") (pinfunction "RXD_17") (pintype "passive"))
      (node (ref "R18") (pin "1") (pinfunction "1_1") (pintype "passive"))
    )
    (net (code "37") (name "/SPI_CLK") (class "Default")
      (node (ref "X14") (pin "1") (pinfunction "1_1") (pintype "passive"))
      (node (ref "X2") (pin "7") (pinfunction "7_7") (pintype "passive"))
    )
    (net (code "38") (name "/SPI_CS1") (class "Default")
      (node (ref "X12") (pin "1") (pinfunction "1_1") (pintype "passive"))
      (node (ref "X2") (pin "8") (pinfunction "8_8") (pintype "passive"))
    )
    (net (code "39") (name "/SPI_CS2") (class "Default")
      (node (ref "X10") (pin "1") (pinfunction "1_1") (pintype "passive"))
      (node (ref "X2") (pin "9") (pinfunction "9_9") (pintype "passive"))
    )
    (net (code "40") (name "/SPI_CS3") (class "Default")
      (node (ref "X2") (pin "10") (pinfunction "10_10") (pintype "passive"))
      (node (ref "X8") (pin "1") (pinfunction "1_1") (pintype "passive"))
    )
    (net (code "41") (name "/SPI_CS4") (class "Default")
      (node (ref "X2") (pin "11") (pinfunction "11_11") (pintype "passive"))
      (node (ref "X6") (pin "1") (pinfunction "1_1") (pintype "passive"))
    )
    (net (code "42") (name "/SPI_MISO") (class "Default")
      (node (ref "X16") (pin "1") (pinfunction "1_1") (pintype "passive"))
      (node (ref "X2") (pin "6") (pinfunction "6_6") (pintype "passive"))
    )
    (net (code "43") (name "/SPI_MOSI") (class "Default")
      (node (ref "X18") (pin "1") (pinfunction "1_1") (pintype "passive"))
      (node (ref "X2") (pin "5") (pinfunction "5_5") (pintype "passive"))
    )
    (net (code "44") (name "/SWCLK") (class "Default")
      (node (ref "X25") (pin "1") (pinfunction "1_1") (pintype "passive"))
      (node (ref "X45") (pin "4") (pinfunction "4_4") (pintype "passive"))
    )
    (net (code "45") (name "/SWDIO") (class "Default")
      (node (ref "X25") (pin "2") (pinfunction "2_2") (pintype "passive"))
      (node (ref "X45") (pin "2") (pinfunction "2_2") (pintype "passive"))
    )
    (net (code "46") (name "/SWO") (class "Default")
      (node (ref "X45") (pin "6") (pinfunction "6_6") (pintype "passive"))
    )
    (net (code "47") (name "/TXD_CP2102") (class "Default")
      (node (ref "IC1") (pin "18") (pinfunction "TXD_18") (pintype "passive"))
      (node (ref "R19") (pin "1") (pinfunction "1_1") (pintype "passive"))
    )
    (net (code "48") (name "/UART1_CTS") (class "Default")
      (node (ref "X1") (pin "9") (pinfunction "9_9") (pintype "passive"))
      (node (ref "X9") (pin "1") (pinfunction "1_1") (pintype "passive"))
    )
    (net (code "49") (name "/UART1_RTS") (class "Default")
      (node (ref "X1") (pin "10") (pinfunction "10_10") (pintype "passive"))
      (node (ref "X7") (pin "1") (pinfunction "1_1") (pintype "passive"))
    )
    (net (code "50") (name "/UART1_RX") (class "Default")
      (node (ref "R19") (pin "2") (pinfunction "2_2") (pintype "passive"))
      (node (ref "X1") (pin "12") (pinfunction "12_12") (pintype "passive"))
      (node (ref "X3") (pin "1") (pinfunction "1_1") (pintype "passive"))
    )
    (net (code "51") (name "/UART1_TX") (class "Default")
      (node (ref "R18") (pin "2") (pinfunction "2_2") (pintype "passive"))
      (node (ref "X1") (pin "11") (pinfunction "11_11") (pintype "passive"))
      (node (ref "X5") (pin "1") (pinfunction "1_1") (pintype "passive"))
    )
    (net (code "52") (name "/UART2_RX") (class "Default")
      (node (ref "X1") (pin "8") (pinfunction "8_8") (pintype "passive"))
      (node (ref "X11") (pin "1") (pinfunction "1_1") (pintype "passive"))
    )
    (net (code "53") (name "/UART2_TX") (class "Default")
      (node (ref "X1") (pin "7") (pinfunction "7_7") (pintype "passive"))
      (node (ref "X13") (pin "1") (pinfunction "1_1") (pintype "passive"))
    )
    (net (code "54") (name "/USB_0_D1_N") (class "Default")
      (node (ref "R22") (pin "2") (pinfunction "2_2") (pintype "passive"))
      (node (ref "X1") (pin "2") (pinfunction "2_2") (pintype "passive"))
    )
    (net (code "55") (name "/USB_0_D1_P") (class "Default")
      (node (ref "R23") (pin "2") (pinfunction "2_2") (pintype "passive"))
      (node (ref "X1") (pin "1") (pinfunction "1_1") (pintype "passive"))
    )
    (net (code "56") (name "/USB_0_D_N") (class "Default")
      (node (ref "D6") (pin "1") (pinfunction "D1+_1") (pintype "passive"))
      (node (ref "D6") (pin "10") (pinfunction "NC_10") (pintype "passive"))
      (node (ref "R22") (pin "1") (pinfunction "1_1") (pintype "passive"))
      (node (ref "X44") (pin "2") (pinfunction "D-_2") (pintype "passive"))
    )
    (net (code "57") (name "/USB_0_D_P") (class "Default")
      (node (ref "D6") (pin "2") (pinfunction "D1-_2") (pintype "passive"))
      (node (ref "D6") (pin "9") (pinfunction "NC_9") (pintype "passive"))
      (node (ref "R23") (pin "1") (pinfunction "1_1") (pintype "passive"))
      (node (ref "X44") (pin "3") (pinfunction "D+_3") (pintype "passive"))
    )
    (net (code "58") (name "/VBUS_CP2102") (class "Default")
      (node (ref "IC1") (pin "8") (pinfunction "VBUS_8") (pintype "passive"))
      (node (ref "R16") (pin "1") (pinfunction "1_1") (pintype "passive"))
      (node (ref "R17") (pin "2") (pinfunction "2_2") (pintype "passive"))
    )
    (net (code "59") (name "/VDD_CP2102") (class "Default")
      (node (ref "C11") (pin "2") (pinfunction "2_2") (pintype "passive"))
      (node (ref "C12") (pin "2") (pinfunction "2_2") (pintype "passive"))
      (node (ref "IC1") (pin "6") (pinfunction "VDD_6") (pintype "passive"))
      (node (ref "R15") (pin "1") (pinfunction "1_1") (pintype "passive"))
    )
    (net (code "60") (name "/nRESET") (class "Default")
      (node (ref "S5") (pin "1") (pinfunction "1_1") (pintype "passive"))
      (node (ref "S5") (pin "2") (pinfunction "2_2") (pintype "passive"))
      (node (ref "X33") (pin "2") (pinfunction "2_2") (pintype "passive"))
      (node (ref "X45") (pin "10") (pinfunction "10_10") (pintype "passive"))
    )
    (net (code "61") (name "/nRST_CP2102") (class "Default")
      (node (ref "IC1") (pin "9") (pinfunction "~{RST}_9") (pintype "passive"))
      (node (ref "R15") (pin "2") (pinfunction "2_2") (pintype "passive"))
    )
    (net (code "62") (name "3V3") (class "Default")
      (node (ref "C6") (pin "1") (pinfunction "1_1") (pintype "passive"))
      (node (ref "C9") (pin "1") (pinfunction "1_1") (pintype "passive"))
      (node (ref "L1") (pin "1") (pinfunction "1_1") (pintype "passive"))
      (node (ref "R1") (pin "2") (pinfunction "2_2") (pintype "passive"))
      (node (ref "R10") (pin "1") (pinfunction "1_1") (pintype "passive"))
      (node (ref "R14") (pin "2") (pinfunction "2_2") (pintype "passive"))
      (node (ref "R2") (pin "2") (pinfunction "2_2") (pintype "passive"))
      (node (ref "R8") (pin "2") (pinfunction "2_2") (pintype "passive"))
      (node (ref "VR1") (pin "2") (pinfunction "Vout_2") (pintype "passive"))
      (node (ref "X33") (pin "5") (pinfunction "5_5") (pintype "passive"))
      (node (ref "X41") (pin "1") (pinfunction "1_1") (pintype "passive"))
      (node (ref "X42") (pin "1") (pinfunction "1_1") (pintype "passive"))
      (node (ref "X45") (pin "1") (pinfunction "1_1") (pintype "passive"))
      (node (ref "X49") (pin "1") (pinfunction "1_1") (pintype "passive"))
      (node (ref "X50") (pin "1") (pinfunction "1_1") (pintype "passive"))
      (node (ref "X51") (pin "1") (pinfunction "1_1") (pintype "passive"))
    )
    (net (code "63") (name "3V3A") (class "Default")
      (node (ref "C10") (pin "1") (pinfunction "1_1") (pintype "passive"))
      (node (ref "L1") (pin "2") (pinfunction "2_2") (pintype "passive"))
      (node (ref "R13") (pin "3") (pinfunction "3_3") (pintype "passive"))
      (node (ref "R6") (pin "3") (pinfunction "3_3") (pintype "passive"))
      (node (ref "X33") (pin "4") (pinfunction "4_4") (pintype "passive"))
      (node (ref "X41") (pin "2") (pinfunction "2_2") (pintype "passive"))
      (node (ref "X48") (pin "1") (pinfunction "1_1") (pintype "passive"))
    )
    (net (code "64") (name "5V0") (class "Default")
      (node (ref "C5") (pin "1") (pinfunction "1_1") (pintype "passive"))
      (node (ref "D10") (pin "2") (pinfunction "K_2") (pintype "passive"))
      (node (ref "D8") (pin "2") (pinfunction "K_2") (pintype "passive"))
      (node (ref "D9") (pin "2") (pinfunction "K_2") (pintype "passive"))
      (node (ref "R24") (pin "1") (pinfunction "1_1") (pintype "passive"))
      (node (ref "VR1") (pin "3") (pinfunction "Vin_3") (pintype "passive"))
    )
    (net (code "65") (name "GND") (class "Default")
      (node (ref "C1") (pin "2") (pinfunction "2_2") (pintype "passive"))
      (node (ref "C10") (pin "2") (pinfunction "2_2") (pintype "passive"))
      (node (ref "C11") (pin "1") (pinfunction "1_1") (pintype "passive"))
      (node (ref "C12") (pin "1") (pinfunction "1_1") (pintype "passive"))
      (node (ref "C13") (pin "1") (pinfunction "1_1") (pintype "passive"))
      (node (ref "C14") (pin "1") (pinfunction "1_1") (pintype "passive"))
      (node (ref "C2") (pin "2") (pinfunction "2_2") (pintype "passive"))
      (node (ref "C3") (pin "2") (pinfunction "2_2") (pintype "passive"))
      (node (ref "C4") (pin "2") (pinfunction "2_2") (pintype "passive"))
      (node (ref "C5") (pin "2") (pinfunction "2_2") (pintype "passive"))
      (node (ref "C6") (pin "2") (pinfunction "2_2") (pintype "passive"))
      (node (ref "C7") (pin "2") (pinfunction "2_2") (pintype "passive"))
      (node (ref "C8") (pin "2") (pinfunction "2_2") (pintype "passive"))
      (node (ref "C9") (pin "2") (pinfunction "2_2") (pintype "passive"))
      (node (ref "D5") (pin "K") (pinfunction "K_K") (pintype "passive"))
      (node (ref "D6") (pin "3") (pinfunction "GND_3") (pintype "power_in"))
      (node (ref "D6") (pin "8") (pinfunction "GND_8") (pintype "power_in"))
      (node (ref "D7") (pin "3") (pinfunction "GND_3") (pintype "power_in"))
      (node (ref "D7") (pin "8") (pinfunction "GND_8") (pintype "power_in"))
      (node (ref "IC1") (pin "12") (pinfunction "GND_12") (pintype "passive"))
      (node (ref "IC1") (pin "21") (pinfunction "GND_21") (pintype "passive"))
      (node (ref "IC1") (pin "3") (pinfunction "GND_3") (pintype "passive"))
      (node (ref "R13") (pin "1") (pinfunction "1_1") (pintype "passive"))
      (node (ref "R16") (pin "2") (pinfunction "2_2") (pintype "passive"))
      (node (ref "R3") (pin "1") (pinfunction "1_1") (pintype "passive"))
      (node (ref "R4") (pin "1") (pinfunction "1_1") (pintype "passive"))
      (node (ref "R6") (pin "1") (pinfunction "1_1") (pintype "passive"))
      (node (ref "R7") (pin "1") (pinfunction "1_1") (pintype "passive"))
      (node (ref "R9") (pin "1") (pinfunction "1_1") (pintype "passive"))
      (node (ref "S1") (pin "3") (pinfunction "3_3") (pintype "passive"))
      (node (ref "S1") (pin "4") (pinfunction "4_4") (pintype "passive"))
      (node (ref "S2") (pin "3") (pinfunction "3_3") (pintype "passive"))
      (node (ref "S2") (pin "4") (pinfunction "4_4") (pintype "passive"))
      (node (ref "S3") (pin "3") (pinfunction "3_3") (pintype "passive"))
      (node (ref "S3") (pin "4") (pinfunction "4_4") (pintype "passive"))
      (node (ref "S4") (pin "3") (pinfunction "3_3") (pintype "passive"))
      (node (ref "S4") (pin "4") (pinfunction "4_4") (pintype "passive"))
      (node (ref "S5") (pin "3") (pinfunction "3_3") (pintype "passive"))
      (node (ref "S5") (pin "4") (pinfunction "4_4") (pintype "passive"))
      (node (ref "VR1") (pin "1") (pinfunction "GND_1") (pintype "passive"))
      (node (ref "X33") (pin "1") (pinfunction "1_1") (pintype "passive"))
      (node (ref "X33") (pin "3") (pinfunction "3_3") (pintype "passive"))
      (node (ref "X44") (pin "4") (pinfunction "ID_4") (pintype "passive"))
      (node (ref "X44") (pin "5") (pinfunction "GND_5") (pintype "power_in"))
      (node (ref "X44") (pin "6") (pinfunction "Shield_6") (pintype "power_in"))
      (node (ref "X45") (pin "3") (pinfunction "3_3") (pintype "passive"))
      (node (ref "X45") (pin "5") (pinfunction "5_5") (pintype "passive"))
      (node (ref "X45") (pin "9") (pinfunction "9_9") (pintype "passive"))
      (node (ref "X46") (pin "4") (pinfunction "ID_4") (pintype "passive"))
      (node (ref "X46") (pin "5") (pinfunction "GND_5") (pintype "power_in"))
      (node (ref "X46") (pin "6") (pinfunction "Shield_6") (pintype "power_in"))
      (node (ref "X47") (pin "2") (pinfunction "2_2") (pintype "passive"))
      (node (ref "X52") (pin "1") (pinfunction "1_1") (pintype "passive"))
      (node (ref "X53") (pin "1") (pinfunction "1_1") (pintype "passive"))
      (node (ref "X54") (pin "1") (pinfunction "1_1") (pintype "passive"))
      (node (ref "X55") (pin "1") (pinfunction "1_1") (pintype "passive"))
      (node (ref "X56") (pin "1") (pinfunction "1_1") (pintype "passive"))
      (node (ref "X57") (pin "1") (pinfunction "1_1") (pintype "passive"))
      (node (ref "X58") (pin "1") (pinfunction "1_1") (pintype "passive"))
      (node (ref "X59") (pin "1") (pinfunction "1_1") (pintype "passive"))
      (node (ref "X60") (pin "1") (pinfunction "1_1") (pintype "passive"))
      (node (ref "X61") (pin "1") (pinfunction "1_1") (pintype "passive"))
      (node (ref "X62") (pin "1") (pinfunction "1_1") (pintype "passive"))
      (node (ref "X63") (pin "1") (pinfunction "1_1") (pintype "passive"))
      (node (ref "X64") (pin "1") (pinfunction "1_1") (pintype "passive"))
      (node (ref "X65") (pin "1") (pinfunction "1_1") (pintype "passive"))
    )
    (net (code "66") (name "Net-(C3-Pad1)") (class "Default")
      (node (ref "C3") (pin "1") (pinfunction "1_1") (pintype "passive"))
      (node (ref "R20") (pin "1") (pinfunction "1_1") (pintype "passive"))
      (node (ref "R5") (pin "1") (pinfunction "1_1") (pintype "passive"))
    )
    (net (code "67") (name "Net-(C7-Pad1)") (class "Default")
      (node (ref "C7") (pin "1") (pinfunction "1_1") (pintype "passive"))
      (node (ref "R12") (pin "1") (pinfunction "1_1") (pintype "passive"))
      (node (ref "R21") (pin "1") (pinfunction "1_1") (pintype "passive"))
    )
    (net (code "68") (name "Net-(D1-PadK)") (class "Default")
      (node (ref "D1") (pin "K") (pinfunction "K_K") (pintype "passive"))
      (node (ref "R3") (pin "2") (pinfunction "2_2") (pintype "passive"))
    )
    (net (code "69") (name "Net-(D2-PadK)") (class "Default")
      (node (ref "D2") (pin "K") (pinfunction "K_K") (pintype "passive"))
      (node (ref "R4") (pin "2") (pinfunction "2_2") (pintype "passive"))
    )
    (net (code "70") (name "Net-(D3-PadK)") (class "Default")
      (node (ref "D3") (pin "K") (pinfunction "K_K") (pintype "passive"))
      (node (ref "R7") (pin "2") (pinfunction "2_2") (pintype "passive"))
    )
    (net (code "71") (name "Net-(D4-PadK)") (class "Default")
      (node (ref "D4") (pin "K") (pinfunction "K_K") (pintype "passive"))
      (node (ref "R9") (pin "2") (pinfunction "2_2") (pintype "passive"))
    )
    (net (code "72") (name "Net-(D5-PadA)") (class "Default")
      (node (ref "D5") (pin "A") (pinfunction "A_A") (pintype "passive"))
      (node (ref "R10") (pin "2") (pinfunction "2_2") (pintype "passive"))
    )
    (net (code "73") (name "Net-(D8-A)") (class "Default")
      (node (ref "D8") (pin "1") (pinfunction "A_1") (pintype "passive"))
      (node (ref "X43") (pin "1") (pinfunction "1_1") (pintype "passive"))
    )
    (net (code "74") (name "Net-(D9-A)") (class "Default")
      (node (ref "D9") (pin "1") (pinfunction "A_1") (pintype "passive"))
      (node (ref "X66") (pin "1") (pinfunction "1_1") (pintype "passive"))
    )
    (net (code "75") (name "Net-(D10-A)") (class "Default")
      (node (ref "D10") (pin "1") (pinfunction "A_1") (pintype "passive"))
      (node (ref "R24") (pin "2") (pinfunction "2_2") (pintype "passive"))
      (node (ref "X47") (pin "1") (pinfunction "1_1") (pintype "passive"))
    )
    (net (code "76") (name "Net-(L2-Pad1)") (class "Default")
      (node (ref "L2") (pin "1") (pinfunction "1_1") (pintype "passive"))
      (node (ref "X43") (pin "2") (pinfunction "2_2") (pintype "passive"))
    )
    (net (code "77") (name "Net-(R5-Pad2)") (class "Default")
      (node (ref "R5") (pin "2") (pinfunction "2_2") (pintype "passive"))
      (node (ref "R6") (pin "2") (pinfunction "2_2") (pintype "passive"))
    )
    (net (code "78") (name "Net-(R12-Pad2)") (class "Default")
      (node (ref "R12") (pin "2") (pinfunction "2_2") (pintype "passive"))
      (node (ref "R13") (pin "2") (pinfunction "2_2") (pintype "passive"))
    )
    (net (code "79") (name "Net-(X44-VBUS)") (class "Default")
      (node (ref "L2") (pin "2") (pinfunction "2_2") (pintype "passive"))
      (node (ref "X44") (pin "1") (pinfunction "VBUS_1") (pintype "power_in"))
    )
    (net (code "80") (name "Net-(X46-VBUS)") (class "Default")
      (node (ref "L3") (pin "2") (pinfunction "2_2") (pintype "passive"))
      (node (ref "X46") (pin "1") (pinfunction "VBUS_1") (pintype "power_in"))
    )
    (net (code "81") (name "VBUS") (class "Default")
      (node (ref "C13") (pin "2") (pinfunction "2_2") (pintype "passive"))
      (node (ref "C14") (pin "2") (pinfunction "2_2") (pintype "passive"))
      (node (ref "IC1") (pin "7") (pinfunction "VREGIN_7") (pintype "passive"))
      (node (ref "L3") (pin "1") (pinfunction "1_1") (pintype "passive"))
      (node (ref "R17") (pin "1") (pinfunction "1_1") (pintype "passive"))
      (node (ref "X66") (pin "2") (pinfunction "2_2") (pintype "passive"))
    )
    (net (code "82") (name "unconnected-(D6-D2+-Pad4)") (class "Default")
      (node (ref "D6") (pin "4") (pinfunction "D2+_4") (pintype "passive+no_connect"))
    )
    (net (code "83") (name "unconnected-(D6-D2--Pad5)") (class "Default")
      (node (ref "D6") (pin "5") (pinfunction "D2-_5") (pintype "passive+no_connect"))
    )
    (net (code "84") (name "unconnected-(D6-NC-Pad6)") (class "Default")
      (node (ref "D6") (pin "6") (pinfunction "NC_6") (pintype "passive+no_connect"))
    )
    (net (code "85") (name "unconnected-(D6-NC-Pad7)") (class "Default")
      (node (ref "D6") (pin "7") (pinfunction "NC_7") (pintype "passive+no_connect"))
    )
    (net (code "86") (name "unconnected-(D7-D2+-Pad4)") (class "Default")
      (node (ref "D7") (pin "4") (pinfunction "D2+_4") (pintype "passive+no_connect"))
    )
    (net (code "87") (name "unconnected-(D7-D2--Pad5)") (class "Default")
      (node (ref "D7") (pin "5") (pinfunction "D2-_5") (pintype "passive+no_connect"))
    )
    (net (code "88") (name "unconnected-(D7-NC-Pad6)") (class "Default")
      (node (ref "D7") (pin "6") (pinfunction "NC_6") (pintype "passive+no_connect"))
    )
    (net (code "89") (name "unconnected-(D7-NC-Pad7)") (class "Default")
      (node (ref "D7") (pin "7") (pinfunction "NC_7") (pintype "passive+no_connect"))
    )
  )
)
